# TopLevel.net
KiCad netlist of a schematic drawn in Altium Designer
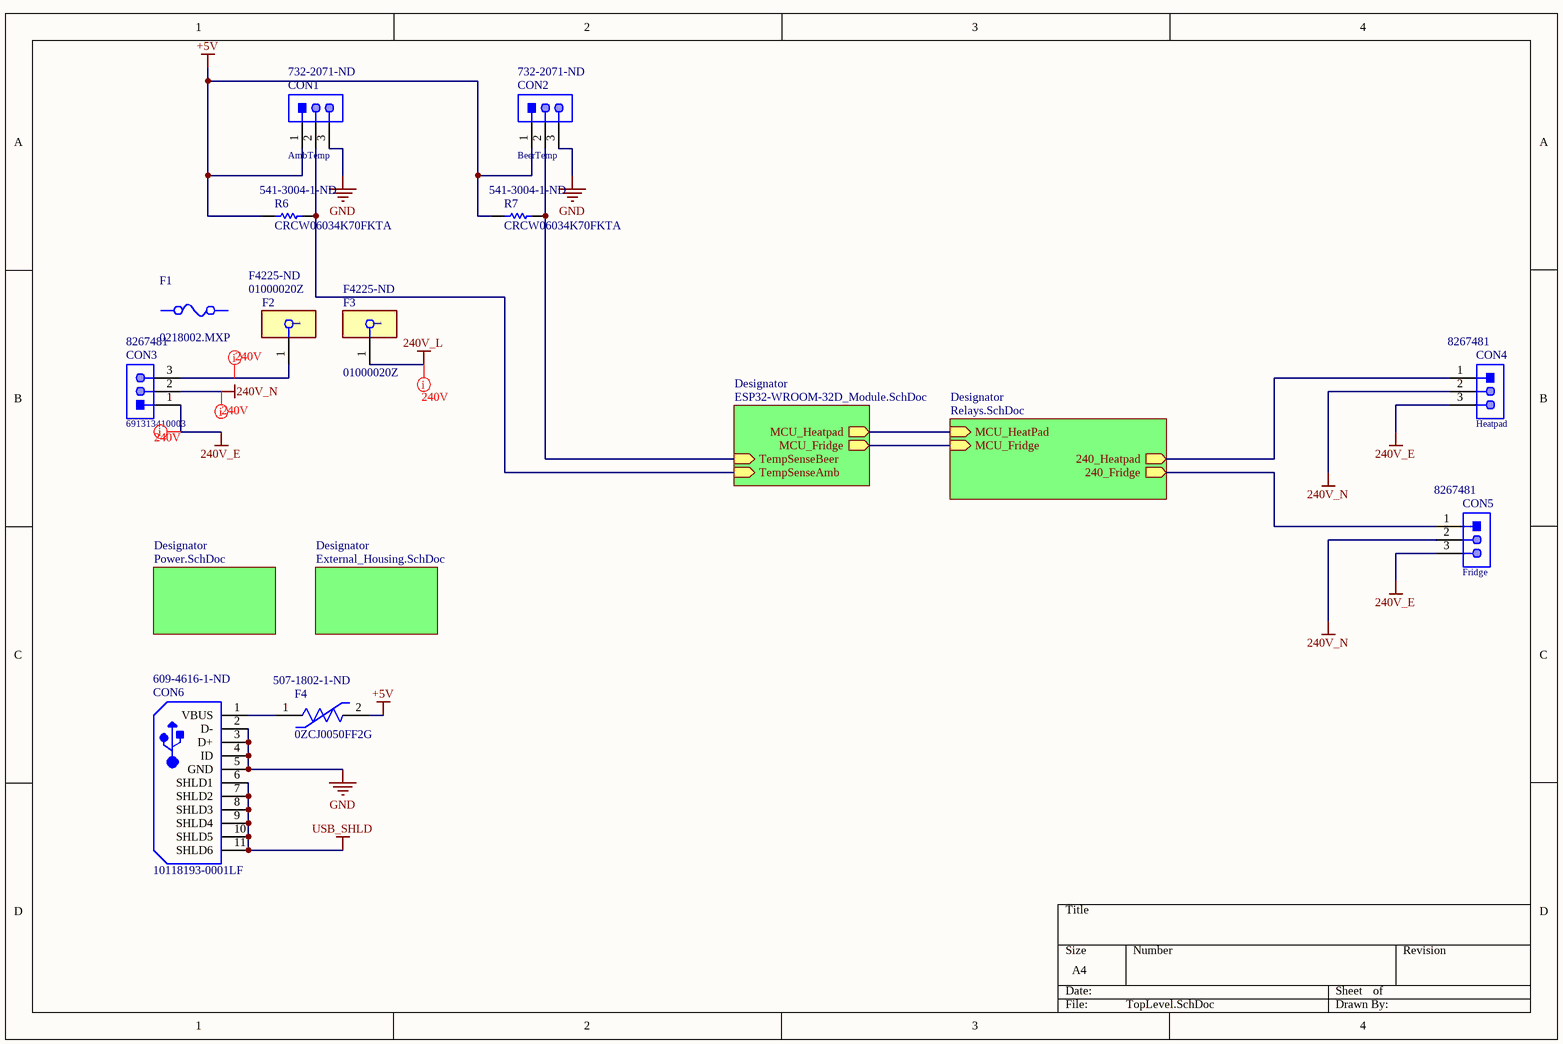
[diagram p0: TopLevel.SchDoc]

(export (version "E")
  (design (tool "Eeschema 10.0.6"))
  (components
    (comp (ref "CON1")
      (value "AmbTemp")
      (footprint "691313510003")
      (description "Serie 313 - 5.08mm Close Horizontal PCB Header WR-TBL, 3 pin")
      (fields
        (field (name "MANUFACTURER") "Wurth Elektronik")
        (field (name "PART NUMBER") "691313510003")
        (field (name "SUPPLIER PART NUMBER 1") "732-2071-ND")
        (field (name "PUBLISHER") "WurthElektronik")
      )
      (libsource (lib "Altium Content Vault") (part "WE-CN-1P-M-R3"))
    )
    (comp (ref "CON2")
      (value "BeerTemp")
      (footprint "691313510003")
      (description "Serie 313 - 5.08mm Close Horizontal PCB Header WR-TBL, 3 pin")
      (fields
        (field (name "MANUFACTURER") "Wurth Elektronik")
        (field (name "PART NUMBER") "691313510003")
        (field (name "SUPPLIER PART NUMBER 1") "732-2071-ND")
        (field (name "PUBLISHER") "WurthElektronik")
      )
      (libsource (lib "Altium Content Vault") (part "WE-CN-1P-M-R3"))
    )
    (comp (ref "CON3")
      (value "691313410003")
      (footprint "691313410003")
      (description "Serie 3134 - 7.62mm Close Horizontal PCB Header WR-TBL, 3 pin")
      (fields
        (field (name "MANUFACTURER") "Wurth Elektronik")
        (field (name "SUPPLIER PART NUMBER 1") "8267481")
        (field (name "VOLTAGE") "300V")
        (field (name "PUBLISHER") "WurthElektronik")
      )
      (libsource (lib "") (part "WE-CN-1P-M-R3_2"))
    )
    (comp (ref "CON4")
      (value "Heatpad")
      (footprint "691313410003")
      (description "Serie 3134 - 7.62mm Close Horizontal PCB Header WR-TBL, 3 pin")
      (fields
        (field (name "MANUFACTURER") "Wurth Elektronik")
        (field (name "PART NUMBER") "691313410003")
        (field (name "SUPPLIER PART NUMBER 1") "8267481")
        (field (name "PUBLISHER") "WurthElektronik")
      )
      (libsource (lib "") (part "WE-CN-1P-M-R3_1"))
    )
    (comp (ref "CON5")
      (value "Fridge")
      (footprint "691313410003")
      (description "Serie 3134 - 7.62mm Close Horizontal PCB Header WR-TBL, 3 pin")
      (fields
        (field (name "MANUFACTURER") "Wurth Elektronik")
        (field (name "PART NUMBER") "691313410003")
        (field (name "SUPPLIER PART NUMBER 1") "8267481")
        (field (name "PUBLISHER") "WurthElektronik")
      )
      (libsource (lib "") (part "WE-CN-1P-M-R3_1"))
    )
    (comp (ref "CON6")
      (value "10118193-0001LF")
      (footprint "FCI-10118193-0001LF-5_V")
      (description "Micro USB B Type Receptacle, -55 to 85 degC, 5-Pin SMD, RoHS, Tape and Reel")
      (fields (field (name "MANUFACTURER") "FCI") (field (name "SUPPLIER PART NUMBER 1") "609-4616-1-ND"))
      (libsource (lib "Altium Content Vault") (part "USB-5-6SHLD"))
    )
    (comp (ref "F1")
      (value "0218002.MXP")
      (footprint "FP-0218002_MXP-MFG")
      (description "FUSE GLASS 2A 250VAC 5X20MM")
      (fields
        (field (name "MANUFACTURER") "Littelfuse Inc")
        (field (name "OCTOPART") "https://octopart.com/0218002.mxp-littelfuse-558306")
      )
      (libsource (lib "Altium Content Vault") (part "ebeb5362a624096d9a0dad9cc630dfd"))
    )
    (comp (ref "F2")
      (value "01000020Z")
      (footprint "FP-0100-MFG")
      (description "FUSE CLIP CARTRIDGE 600V 20A PCB")
      (fields
        (field (name "VOLTAGE") "600V")
        (field (name "SUPPLIER PART NUMBER 1") "F4225-ND")
        (field (name "MANUFACTURER") "Littelfuse")
      )
      (libsource (lib "Altium Content Vault") (part "c5c826e0c4b67fe3b42ef77f2d4decc"))
    )
    (comp (ref "F3")
      (value "01000020Z")
      (footprint "FP-0100-MFG")
      (description "FUSE CLIP CARTRIDGE 600V 20A PCB")
      (fields
        (field (name "VOLTAGE") "600V")
        (field (name "SUPPLIER PART NUMBER 1") "F4225-ND")
        (field (name "MANUFACTURER") "Littelfuse")
      )
      (libsource (lib "Altium Content Vault") (part "c5c826e0c4b67fe3b42ef77f2d4decc"))
    )
    (comp (ref "F4")
      (value "0ZCJ0050FF2G")
      (footprint "FP-0ZCJ0050FF2G-MFG")
      (description "PTC RESET FUSE 8V 500MA 1206")
      (fields (field (name "SUPPLIER PART NUMBER 1") "507-1802-1-ND") (field (name "MANUFACTURER") "Bel"))
      (libsource (lib "Altium Content Vault") (part "1c6d77a0208143737455a0c7eb396be"))
    )
    (comp (ref "R6")
      (value "CRCW06034K70FKTA")
      (footprint "RESC1609X50X30NL10T20")
      (description "0603 4K7")
      (fields
        (field (name "MANUFACTURER") "Vishay Dale")
        (field (name "SUPPLIER PART NUMBER 1") "541-3004-1-ND")
        (field (name "TOLERANCE") "1%")
      )
      (libsource (lib "Altium Content Vault") (part "RES"))
    )
    (comp (ref "R7")
      (value "CRCW06034K70FKTA")
      (footprint "RESC1609X50X30NL10T20")
      (description "0603 4K7")
      (fields
        (field (name "MANUFACTURER") "Vishay Dale")
        (field (name "SUPPLIER PART NUMBER 1") "541-3004-1-ND")
        (field (name "TOLERANCE") "1%")
      )
      (libsource (lib "Altium Content Vault") (part "RES"))
    )
  )
  (nets
    (net (code "1") (name "+5V") (class "Default")
      (node (ref "CON1") (pin "1") (pinfunction "1_1") (pintype "passive"))
      (node (ref "CON2") (pin "1") (pinfunction "1_1") (pintype "passive"))
      (node (ref "F4") (pin "2") (pinfunction "2_2") (pintype "passive"))
      (node (ref "R6") (pin "1") (pinfunction "1_1") (pintype "passive"))
      (node (ref "R7") (pin "1") (pinfunction "1_1") (pintype "passive"))
    )
    (net (code "2") (name "/240_Fridge") (class "Default")
      (node (ref "CON5") (pin "1") (pinfunction "1_1") (pintype "passive"))
    )
    (net (code "3") (name "/240_Heatpad") (class "Default")
      (node (ref "CON4") (pin "1") (pinfunction "1_1") (pintype "passive"))
    )
    (net (code "6") (name "/TempSenseAmb") (class "Default")
      (node (ref "CON1") (pin "2") (pinfunction "2_2") (pintype "passive"))
      (node (ref "R6") (pin "2") (pinfunction "2_2") (pintype "passive"))
    )
    (net (code "7") (name "/TempSenseBeer") (class "Default")
      (node (ref "CON2") (pin "2") (pinfunction "2_2") (pintype "passive"))
      (node (ref "R7") (pin "2") (pinfunction "2_2") (pintype "passive"))
    )
    (net (code "8") (name "240V_E") (class "Default")
      (node (ref "CON3") (pin "1") (pinfunction "1_1") (pintype "passive"))
      (node (ref "CON4") (pin "3") (pinfunction "3_3") (pintype "passive"))
      (node (ref "CON5") (pin "3") (pinfunction "3_3") (pintype "passive"))
    )
    (net (code "9") (name "240V_L") (class "Default")
      (node (ref "F3") (pin "1") (pinfunction "1_1") (pintype "passive"))
    )
    (net (code "10") (name "240V_N") (class "Default")
      (node (ref "CON3") (pin "2") (pinfunction "2_2") (pintype "passive"))
      (node (ref "CON4") (pin "2") (pinfunction "2_2") (pintype "passive"))
      (node (ref "CON5") (pin "2") (pinfunction "2_2") (pintype "passive"))
    )
    (net (code "11") (name "GND") (class "Default")
      (node (ref "CON1") (pin "3") (pinfunction "3_3") (pintype "passive"))
      (node (ref "CON2") (pin "3") (pinfunction "3_3") (pintype "passive"))
      (node (ref "CON6") (pin "2") (pinfunction "D-_2") (pintype "passive"))
      (node (ref "CON6") (pin "3") (pinfunction "D+_3") (pintype "passive"))
      (node (ref "CON6") (pin "4") (pinfunction "ID_4") (pintype "passive"))
      (node (ref "CON6") (pin "5") (pinfunction "GND_5") (pintype "passive"))
    )
    (net (code "12") (name "Net-(CON3-Pad3)") (class "Default")
      (node (ref "CON3") (pin "3") (pinfunction "3_3") (pintype "passive"))
      (node (ref "F2") (pin "1") (pinfunction "1_1") (pintype "passive"))
    )
    (net (code "13") (name "Net-(CON6-VBUS)") (class "Default")
      (node (ref "CON6") (pin "1") (pinfunction "VBUS_1") (pintype "passive"))
      (node (ref "F4") (pin "1") (pinfunction "1_1") (pintype "passive"))
    )
    (net (code "14") (name "USB_SHLD") (class "Default")
      (node (ref "CON6") (pin "10") (pinfunction "SHLD5_10") (pintype "passive"))
      (node (ref "CON6") (pin "11") (pinfunction "SHLD6_11") (pintype "passive"))
      (node (ref "CON6") (pin "6") (pinfunction "SHLD1_6") (pintype "passive"))
      (node (ref "CON6") (pin "7") (pinfunction "SHLD2_7") (pintype "passive"))
      (node (ref "CON6") (pin "8") (pinfunction "SHLD3_8") (pintype "passive"))
      (node (ref "CON6") (pin "9") (pinfunction "SHLD4_9") (pintype "passive"))
    )
  )
)
